# FlashPak.net
KiCad netlist of a schematic drawn in EAGLE
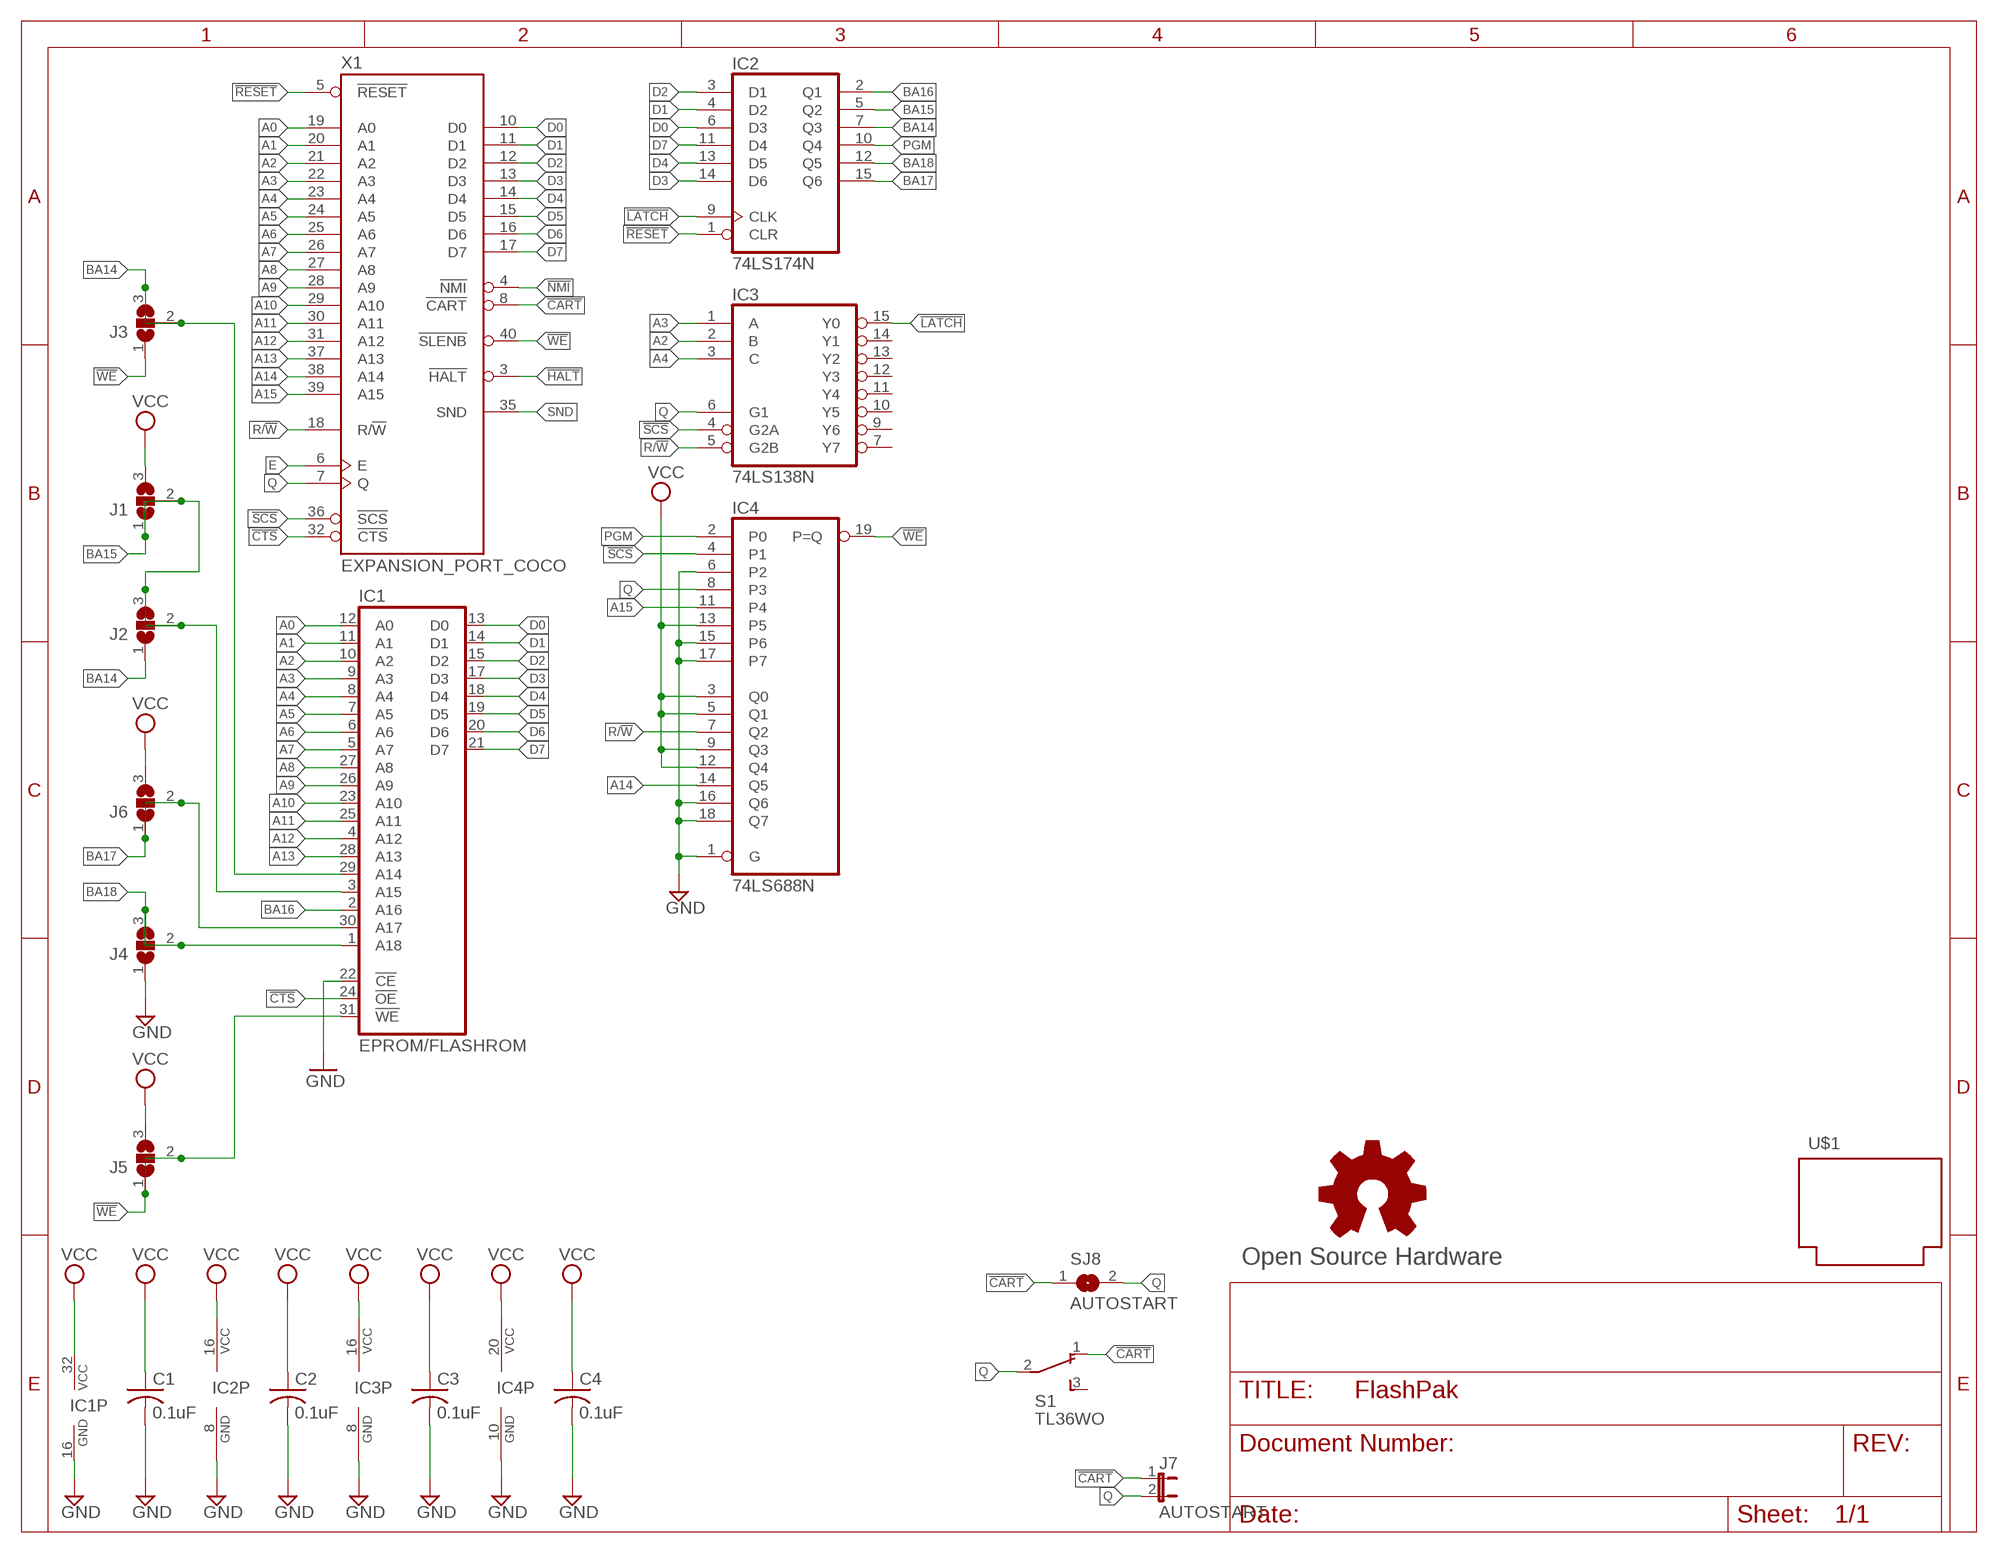
[diagram p0: schematic, sheet 1]

(export (version "E")
  (design (tool "Eeschema 10.0.6"))
  (components
    (comp (ref "C1")
      (value "0.1uF")
      (footprint "eagle-import:C025-025X050")
      (libsource (lib "eagle-import") (part "C-US025-025X050"))
    )
    (comp (ref "C2")
      (value "0.1uF")
      (footprint "eagle-import:C025-025X050")
      (libsource (lib "eagle-import") (part "C-US025-025X050"))
    )
    (comp (ref "C3")
      (value "0.1uF")
      (footprint "eagle-import:C025-025X050")
      (libsource (lib "eagle-import") (part "C-US025-025X050"))
    )
    (comp (ref "C4")
      (value "0.1uF")
      (footprint "eagle-import:C025-025X050")
      (libsource (lib "eagle-import") (part "C-US025-025X050"))
    )
    (comp (ref "GOLD_ORB_SM1")
      (value "Open Source Hardware")
      (footprint "eagle-import:OSHW_8MM")
      (libsource (lib "eagle-import") (part "OSHWLOGOLOGO8MM"))
    )
    (comp (ref "IC1")
      (value "EPROM/FLASHROM")
      (footprint "eagle-import:DIL32-RP")
      (libsource (lib "eagle-import") (part "SST39SF040APHR"))
    )
    (comp (ref "IC2")
      (value "74LS174N")
      (footprint "eagle-import:DIL16-RP")
      (libsource (lib "eagle-import") (part "74174NLS"))
    )
    (comp (ref "IC3")
      (value "74LS138N")
      (footprint "eagle-import:DIL16-RP")
      (libsource (lib "eagle-import") (part "74138NLS"))
    )
    (comp (ref "IC4")
      (value "74LS688N")
      (footprint "eagle-import:DIL20-RP")
      (libsource (lib "eagle-import") (part "74688NLS"))
    )
    (comp (ref "J1")
      (value "SJ2W")
      (footprint "eagle-import:SJ_2")
      (libsource (lib "eagle-import") (part "SJ2W"))
    )
    (comp (ref "J2")
      (value "SJ2W")
      (footprint "eagle-import:SJ_2")
      (libsource (lib "eagle-import") (part "SJ2W"))
    )
    (comp (ref "J3")
      (value "SJ2W")
      (footprint "eagle-import:SJ_2")
      (libsource (lib "eagle-import") (part "SJ2W"))
    )
    (comp (ref "J4")
      (value "SJ2W")
      (footprint "eagle-import:SJ_2")
      (libsource (lib "eagle-import") (part "SJ2W"))
    )
    (comp (ref "J5")
      (value "SJ2W")
      (footprint "eagle-import:SJ_2")
      (libsource (lib "eagle-import") (part "SJ2W"))
    )
    (comp (ref "J6")
      (value "SJ2W")
      (footprint "eagle-import:SJ_2")
      (libsource (lib "eagle-import") (part "SJ2W"))
    )
    (comp (ref "J7")
      (value "AUTOSTART")
      (footprint "eagle-import:JP1")
      (libsource (lib "eagle-import") (part "JP1E"))
    )
    (comp (ref "S1")
      (value "TL36WO")
      (footprint "eagle-import:TL3XWO")
      (libsource (lib "eagle-import") (part "TL36WO"))
    )
    (comp (ref "SJ8")
      (value "AUTOSTART")
      (footprint "eagle-import:SJ")
      (libsource (lib "eagle-import") (part "SJ"))
    )
    (comp (ref "U$1")
      (value "PROGRAM_PAK")
      (footprint "eagle-import:PROGRAM_PAK")
      (libsource (lib "eagle-import") (part "PROGRAM_PAK"))
    )
    (comp (ref "X1")
      (value "EXPANSION_PORT_COCO")
      (footprint "eagle-import:MA20-2")
      (libsource (lib "eagle-import") (part "EXPANSION_PORT_COCO"))
    )
  )
  (nets
    (net (code "1") (name "/R{slash}~{W}") (class "Default")
      (node (ref "IC3") (pin "5") (pinfunction "G2B_5") (pintype "input"))
      (node (ref "IC4") (pin "7") (pinfunction "Q2_7") (pintype "input"))
      (node (ref "X1") (pin "18") (pinfunction "R/~{W}_18") (pintype "output"))
    )
    (net (code "2") (name "/~{CART}") (class "Default")
      (node (ref "J7") (pin "1") (pinfunction "1_1") (pintype "passive"))
      (node (ref "S1") (pin "1") (pinfunction "O_1") (pintype "passive"))
      (node (ref "SJ8") (pin "1") (pinfunction "1_1") (pintype "passive"))
      (node (ref "X1") (pin "8") (pinfunction "~{CART}_8") (pintype "open_collector"))
    )
    (net (code "3") (name "/~{CTS}") (class "Default")
      (node (ref "IC1") (pin "24") (pinfunction "~{OE}_24") (pintype "input"))
      (node (ref "X1") (pin "32") (pinfunction "~{CTS}_32") (pintype "output"))
    )
    (net (code "4") (name "/~{HALT}") (class "Default")
      (node (ref "X1") (pin "3") (pinfunction "~{HALT}_3") (pintype "open_collector"))
    )
    (net (code "5") (name "/~{LATCH}") (class "Default")
      (node (ref "IC2") (pin "9") (pinfunction "CLK_9") (pintype "input"))
      (node (ref "IC3") (pin "15") (pinfunction "Y0_15") (pintype "output"))
    )
    (net (code "6") (name "/~{NMI}") (class "Default")
      (node (ref "X1") (pin "4") (pinfunction "~{NMI}_4") (pintype "open_collector"))
    )
    (net (code "7") (name "/~{RESET}") (class "Default")
      (node (ref "IC2") (pin "1") (pinfunction "CLR_1") (pintype "input"))
      (node (ref "X1") (pin "5") (pinfunction "~{RESET}_5") (pintype "open_collector"))
    )
    (net (code "8") (name "/~{SCS}") (class "Default")
      (node (ref "IC3") (pin "4") (pinfunction "G2A_4") (pintype "input"))
      (node (ref "IC4") (pin "4") (pinfunction "P1_4") (pintype "input"))
      (node (ref "X1") (pin "36") (pinfunction "~{SCS}_36") (pintype "output"))
    )
    (net (code "9") (name "/~{WE}") (class "Default")
      (node (ref "IC1") (pin "31") (pinfunction "~{WE}_31") (pintype "input"))
      (node (ref "IC4") (pin "19") (pinfunction "P=Q_19") (pintype "output"))
      (node (ref "J3") (pin "1") (pinfunction "1_1") (pintype "passive"))
      (node (ref "J5") (pin "1") (pinfunction "1_1") (pintype "passive"))
      (node (ref "J5") (pin "2") (pinfunction "2_2") (pintype "passive"))
      (node (ref "X1") (pin "40") (pinfunction "~{SLENB}_40") (pintype "open_collector"))
    )
    (net (code "10") (name "A0") (class "Default")
      (node (ref "IC1") (pin "12") (pinfunction "A0_12") (pintype "input"))
      (node (ref "X1") (pin "19") (pinfunction "A0_19") (pintype "output"))
    )
    (net (code "11") (name "A1") (class "Default")
      (node (ref "IC1") (pin "11") (pinfunction "A1_11") (pintype "input"))
      (node (ref "X1") (pin "20") (pinfunction "A1_20") (pintype "output"))
    )
    (net (code "12") (name "A2") (class "Default")
      (node (ref "IC1") (pin "10") (pinfunction "A2_10") (pintype "input"))
      (node (ref "IC3") (pin "2") (pinfunction "B_2") (pintype "input"))
      (node (ref "X1") (pin "21") (pinfunction "A2_21") (pintype "output"))
    )
    (net (code "13") (name "A3") (class "Default")
      (node (ref "IC1") (pin "9") (pinfunction "A3_9") (pintype "input"))
      (node (ref "IC3") (pin "1") (pinfunction "A_1") (pintype "input"))
      (node (ref "X1") (pin "22") (pinfunction "A3_22") (pintype "output"))
    )
    (net (code "14") (name "A4") (class "Default")
      (node (ref "IC1") (pin "8") (pinfunction "A4_8") (pintype "input"))
      (node (ref "IC3") (pin "3") (pinfunction "C_3") (pintype "input"))
      (node (ref "X1") (pin "23") (pinfunction "A4_23") (pintype "output"))
    )
    (net (code "15") (name "A5") (class "Default")
      (node (ref "IC1") (pin "7") (pinfunction "A5_7") (pintype "input"))
      (node (ref "X1") (pin "24") (pinfunction "A5_24") (pintype "output"))
    )
    (net (code "16") (name "A6") (class "Default")
      (node (ref "IC1") (pin "6") (pinfunction "A6_6") (pintype "input"))
      (node (ref "X1") (pin "25") (pinfunction "A6_25") (pintype "output"))
    )
    (net (code "17") (name "A7") (class "Default")
      (node (ref "IC1") (pin "5") (pinfunction "A7_5") (pintype "input"))
      (node (ref "X1") (pin "26") (pinfunction "A7_26") (pintype "output"))
    )
    (net (code "18") (name "A8") (class "Default")
      (node (ref "IC1") (pin "27") (pinfunction "A8_27") (pintype "input"))
      (node (ref "X1") (pin "27") (pinfunction "A8_27") (pintype "output"))
    )
    (net (code "19") (name "A9") (class "Default")
      (node (ref "IC1") (pin "26") (pinfunction "A9_26") (pintype "input"))
      (node (ref "X1") (pin "28") (pinfunction "A9_28") (pintype "output"))
    )
    (net (code "20") (name "A10") (class "Default")
      (node (ref "IC1") (pin "23") (pinfunction "A10_23") (pintype "input"))
      (node (ref "X1") (pin "29") (pinfunction "A10_29") (pintype "output"))
    )
    (net (code "21") (name "A11") (class "Default")
      (node (ref "IC1") (pin "25") (pinfunction "A11_25") (pintype "input"))
      (node (ref "X1") (pin "30") (pinfunction "A11_30") (pintype "output"))
    )
    (net (code "22") (name "A12") (class "Default")
      (node (ref "IC1") (pin "4") (pinfunction "A12_4") (pintype "input"))
      (node (ref "X1") (pin "31") (pinfunction "A12_31") (pintype "output"))
    )
    (net (code "23") (name "A13") (class "Default")
      (node (ref "IC1") (pin "28") (pinfunction "A13_28") (pintype "input"))
      (node (ref "X1") (pin "37") (pinfunction "A13_37") (pintype "output"))
    )
    (net (code "24") (name "A14") (class "Default")
      (node (ref "IC4") (pin "14") (pinfunction "Q5_14") (pintype "input"))
      (node (ref "X1") (pin "38") (pinfunction "A14_38") (pintype "output"))
    )
    (net (code "25") (name "A15") (class "Default")
      (node (ref "IC4") (pin "11") (pinfunction "P4_11") (pintype "input"))
      (node (ref "X1") (pin "39") (pinfunction "A15_39") (pintype "output"))
    )
    (net (code "26") (name "BA14") (class "Default")
      (node (ref "IC1") (pin "29") (pinfunction "A14_29") (pintype "input"))
      (node (ref "IC2") (pin "7") (pinfunction "Q3_7") (pintype "output"))
      (node (ref "J2") (pin "1") (pinfunction "1_1") (pintype "passive"))
      (node (ref "J3") (pin "2") (pinfunction "2_2") (pintype "passive"))
      (node (ref "J3") (pin "3") (pinfunction "3_3") (pintype "passive"))
    )
    (net (code "27") (name "BA15") (class "Default")
      (node (ref "IC1") (pin "3") (pinfunction "A15_3") (pintype "input"))
      (node (ref "IC2") (pin "5") (pinfunction "Q2_5") (pintype "output"))
      (node (ref "J1") (pin "1") (pinfunction "1_1") (pintype "passive"))
      (node (ref "J1") (pin "2") (pinfunction "2_2") (pintype "passive"))
      (node (ref "J2") (pin "2") (pinfunction "2_2") (pintype "passive"))
      (node (ref "J2") (pin "3") (pinfunction "3_3") (pintype "passive"))
    )
    (net (code "28") (name "BA16") (class "Default")
      (node (ref "IC1") (pin "2") (pinfunction "A16_2") (pintype "input"))
      (node (ref "IC2") (pin "2") (pinfunction "Q1_2") (pintype "output"))
    )
    (net (code "29") (name "BA17") (class "Default")
      (node (ref "IC1") (pin "30") (pinfunction "A17_30") (pintype "input"))
      (node (ref "IC2") (pin "15") (pinfunction "Q6_15") (pintype "output"))
      (node (ref "J6") (pin "1") (pinfunction "1_1") (pintype "passive"))
      (node (ref "J6") (pin "2") (pinfunction "2_2") (pintype "passive"))
    )
    (net (code "30") (name "BA18") (class "Default")
      (node (ref "IC1") (pin "1") (pinfunction "A18_1") (pintype "input"))
      (node (ref "IC2") (pin "12") (pinfunction "Q5_12") (pintype "output"))
      (node (ref "J4") (pin "2") (pinfunction "2_2") (pintype "passive"))
      (node (ref "J4") (pin "3") (pinfunction "3_3") (pintype "passive"))
    )
    (net (code "31") (name "D0") (class "Default")
      (node (ref "IC1") (pin "13") (pinfunction "D0_13") (pintype "bidirectional"))
      (node (ref "IC2") (pin "6") (pinfunction "D3_6") (pintype "input"))
      (node (ref "X1") (pin "10") (pinfunction "D0_10") (pintype "bidirectional"))
    )
    (net (code "32") (name "D1") (class "Default")
      (node (ref "IC1") (pin "14") (pinfunction "D1_14") (pintype "bidirectional"))
      (node (ref "IC2") (pin "4") (pinfunction "D2_4") (pintype "input"))
      (node (ref "X1") (pin "11") (pinfunction "D1_11") (pintype "bidirectional"))
    )
    (net (code "33") (name "D2") (class "Default")
      (node (ref "IC1") (pin "15") (pinfunction "D2_15") (pintype "bidirectional"))
      (node (ref "IC2") (pin "3") (pinfunction "D1_3") (pintype "input"))
      (node (ref "X1") (pin "12") (pinfunction "D2_12") (pintype "bidirectional"))
    )
    (net (code "34") (name "D3") (class "Default")
      (node (ref "IC1") (pin "17") (pinfunction "D3_17") (pintype "bidirectional"))
      (node (ref "IC2") (pin "14") (pinfunction "D6_14") (pintype "input"))
      (node (ref "X1") (pin "13") (pinfunction "D3_13") (pintype "bidirectional"))
    )
    (net (code "35") (name "D4") (class "Default")
      (node (ref "IC1") (pin "18") (pinfunction "D4_18") (pintype "bidirectional"))
      (node (ref "IC2") (pin "13") (pinfunction "D5_13") (pintype "input"))
      (node (ref "X1") (pin "14") (pinfunction "D4_14") (pintype "bidirectional"))
    )
    (net (code "36") (name "D5") (class "Default")
      (node (ref "IC1") (pin "19") (pinfunction "D5_19") (pintype "bidirectional"))
      (node (ref "X1") (pin "15") (pinfunction "D5_15") (pintype "bidirectional"))
    )
    (net (code "37") (name "D6") (class "Default")
      (node (ref "IC1") (pin "20") (pinfunction "D6_20") (pintype "bidirectional"))
      (node (ref "X1") (pin "16") (pinfunction "D6_16") (pintype "bidirectional"))
    )
    (net (code "38") (name "D7") (class "Default")
      (node (ref "IC1") (pin "21") (pinfunction "D7_21") (pintype "bidirectional"))
      (node (ref "IC2") (pin "11") (pinfunction "D4_11") (pintype "input"))
      (node (ref "X1") (pin "17") (pinfunction "D7_17") (pintype "bidirectional"))
    )
    (net (code "39") (name "E") (class "Default")
      (node (ref "X1") (pin "6") (pinfunction "E_6") (pintype "output"))
    )
    (net (code "40") (name "GND") (class "Default")
      (node (ref "C1") (pin "2") (pinfunction "2_2") (pintype "passive"))
      (node (ref "C2") (pin "2") (pinfunction "2_2") (pintype "passive"))
      (node (ref "C3") (pin "2") (pinfunction "2_2") (pintype "passive"))
      (node (ref "C4") (pin "2") (pinfunction "2_2") (pintype "passive"))
      (node (ref "IC1") (pin "16") (pinfunction "GND_16") (pintype "power_in"))
      (node (ref "IC1") (pin "22") (pinfunction "~{CE}_22") (pintype "input"))
      (node (ref "IC2") (pin "8") (pinfunction "GND_8") (pintype "power_in"))
      (node (ref "IC3") (pin "8") (pinfunction "GND_8") (pintype "power_in"))
      (node (ref "IC4") (pin "1") (pinfunction "G_1") (pintype "input"))
      (node (ref "IC4") (pin "10") (pinfunction "GND_10") (pintype "power_in"))
      (node (ref "IC4") (pin "15") (pinfunction "P6_15") (pintype "input"))
      (node (ref "IC4") (pin "16") (pinfunction "Q6_16") (pintype "input"))
      (node (ref "IC4") (pin "17") (pinfunction "P7_17") (pintype "input"))
      (node (ref "IC4") (pin "18") (pinfunction "Q7_18") (pintype "input"))
      (node (ref "IC4") (pin "6") (pinfunction "P2_6") (pintype "input"))
      (node (ref "J4") (pin "1") (pinfunction "1_1") (pintype "passive"))
    )
    (net (code "41") (name "PGM") (class "Default")
      (node (ref "IC2") (pin "10") (pinfunction "Q4_10") (pintype "output"))
      (node (ref "IC4") (pin "2") (pinfunction "P0_2") (pintype "input"))
    )
    (net (code "42") (name "Q") (class "Default")
      (node (ref "IC3") (pin "6") (pinfunction "G1_6") (pintype "input"))
      (node (ref "IC4") (pin "8") (pinfunction "P3_8") (pintype "input"))
      (node (ref "J7") (pin "2") (pinfunction "2_2") (pintype "passive"))
      (node (ref "S1") (pin "2") (pinfunction "P_2") (pintype "passive"))
      (node (ref "SJ8") (pin "2") (pinfunction "2_2") (pintype "passive"))
      (node (ref "X1") (pin "7") (pinfunction "Q_7") (pintype "output"))
    )
    (net (code "43") (name "SND") (class "Default")
      (node (ref "X1") (pin "35") (pinfunction "SND_35") (pintype "passive"))
    )
    (net (code "44") (name "VCC") (class "Default")
      (node (ref "C1") (pin "1") (pinfunction "1_1") (pintype "passive"))
      (node (ref "C2") (pin "1") (pinfunction "1_1") (pintype "passive"))
      (node (ref "C3") (pin "1") (pinfunction "1_1") (pintype "passive"))
      (node (ref "C4") (pin "1") (pinfunction "1_1") (pintype "passive"))
      (node (ref "IC1") (pin "32") (pinfunction "VCC_32") (pintype "power_in"))
      (node (ref "IC2") (pin "16") (pinfunction "VCC_16") (pintype "power_in"))
      (node (ref "IC3") (pin "16") (pinfunction "VCC_16") (pintype "power_in"))
      (node (ref "IC4") (pin "12") (pinfunction "Q4_12") (pintype "input"))
      (node (ref "IC4") (pin "13") (pinfunction "P5_13") (pintype "input"))
      (node (ref "IC4") (pin "20") (pinfunction "VCC_20") (pintype "power_in"))
      (node (ref "IC4") (pin "3") (pinfunction "Q0_3") (pintype "input"))
      (node (ref "IC4") (pin "5") (pinfunction "Q1_5") (pintype "input"))
      (node (ref "IC4") (pin "9") (pinfunction "Q3_9") (pintype "input"))
      (node (ref "J1") (pin "3") (pinfunction "3_3") (pintype "passive"))
      (node (ref "J5") (pin "3") (pinfunction "3_3") (pintype "passive"))
      (node (ref "J6") (pin "3") (pinfunction "3_3") (pintype "passive"))
    )
    (net (code "45") (name "unconnected-(IC3A-Y1-Pad14)") (class "Default")
      (node (ref "IC3") (pin "14") (pinfunction "Y1_14") (pintype "output"))
    )
    (net (code "46") (name "unconnected-(IC3A-Y2-Pad13)") (class "Default")
      (node (ref "IC3") (pin "13") (pinfunction "Y2_13") (pintype "output"))
    )
    (net (code "47") (name "unconnected-(IC3A-Y3-Pad12)") (class "Default")
      (node (ref "IC3") (pin "12") (pinfunction "Y3_12") (pintype "output"))
    )
    (net (code "48") (name "unconnected-(IC3A-Y4-Pad11)") (class "Default")
      (node (ref "IC3") (pin "11") (pinfunction "Y4_11") (pintype "output"))
    )
    (net (code "49") (name "unconnected-(IC3A-Y5-Pad10)") (class "Default")
      (node (ref "IC3") (pin "10") (pinfunction "Y5_10") (pintype "output"))
    )
    (net (code "50") (name "unconnected-(IC3A-Y6-Pad9)") (class "Default")
      (node (ref "IC3") (pin "9") (pinfunction "Y6_9") (pintype "output"))
    )
    (net (code "51") (name "unconnected-(IC3A-Y7-Pad7)") (class "Default")
      (node (ref "IC3") (pin "7") (pinfunction "Y7_7") (pintype "output"))
    )
    (net (code "52") (name "unconnected-(S1-S-Pad3)") (class "Default")
      (node (ref "S1") (pin "3") (pinfunction "S_3") (pintype "passive"))
    )
  )
)
